# McPiFace-Pi4-Status-V3.net
KiCad netlist of a schematic drawn in EAGLE
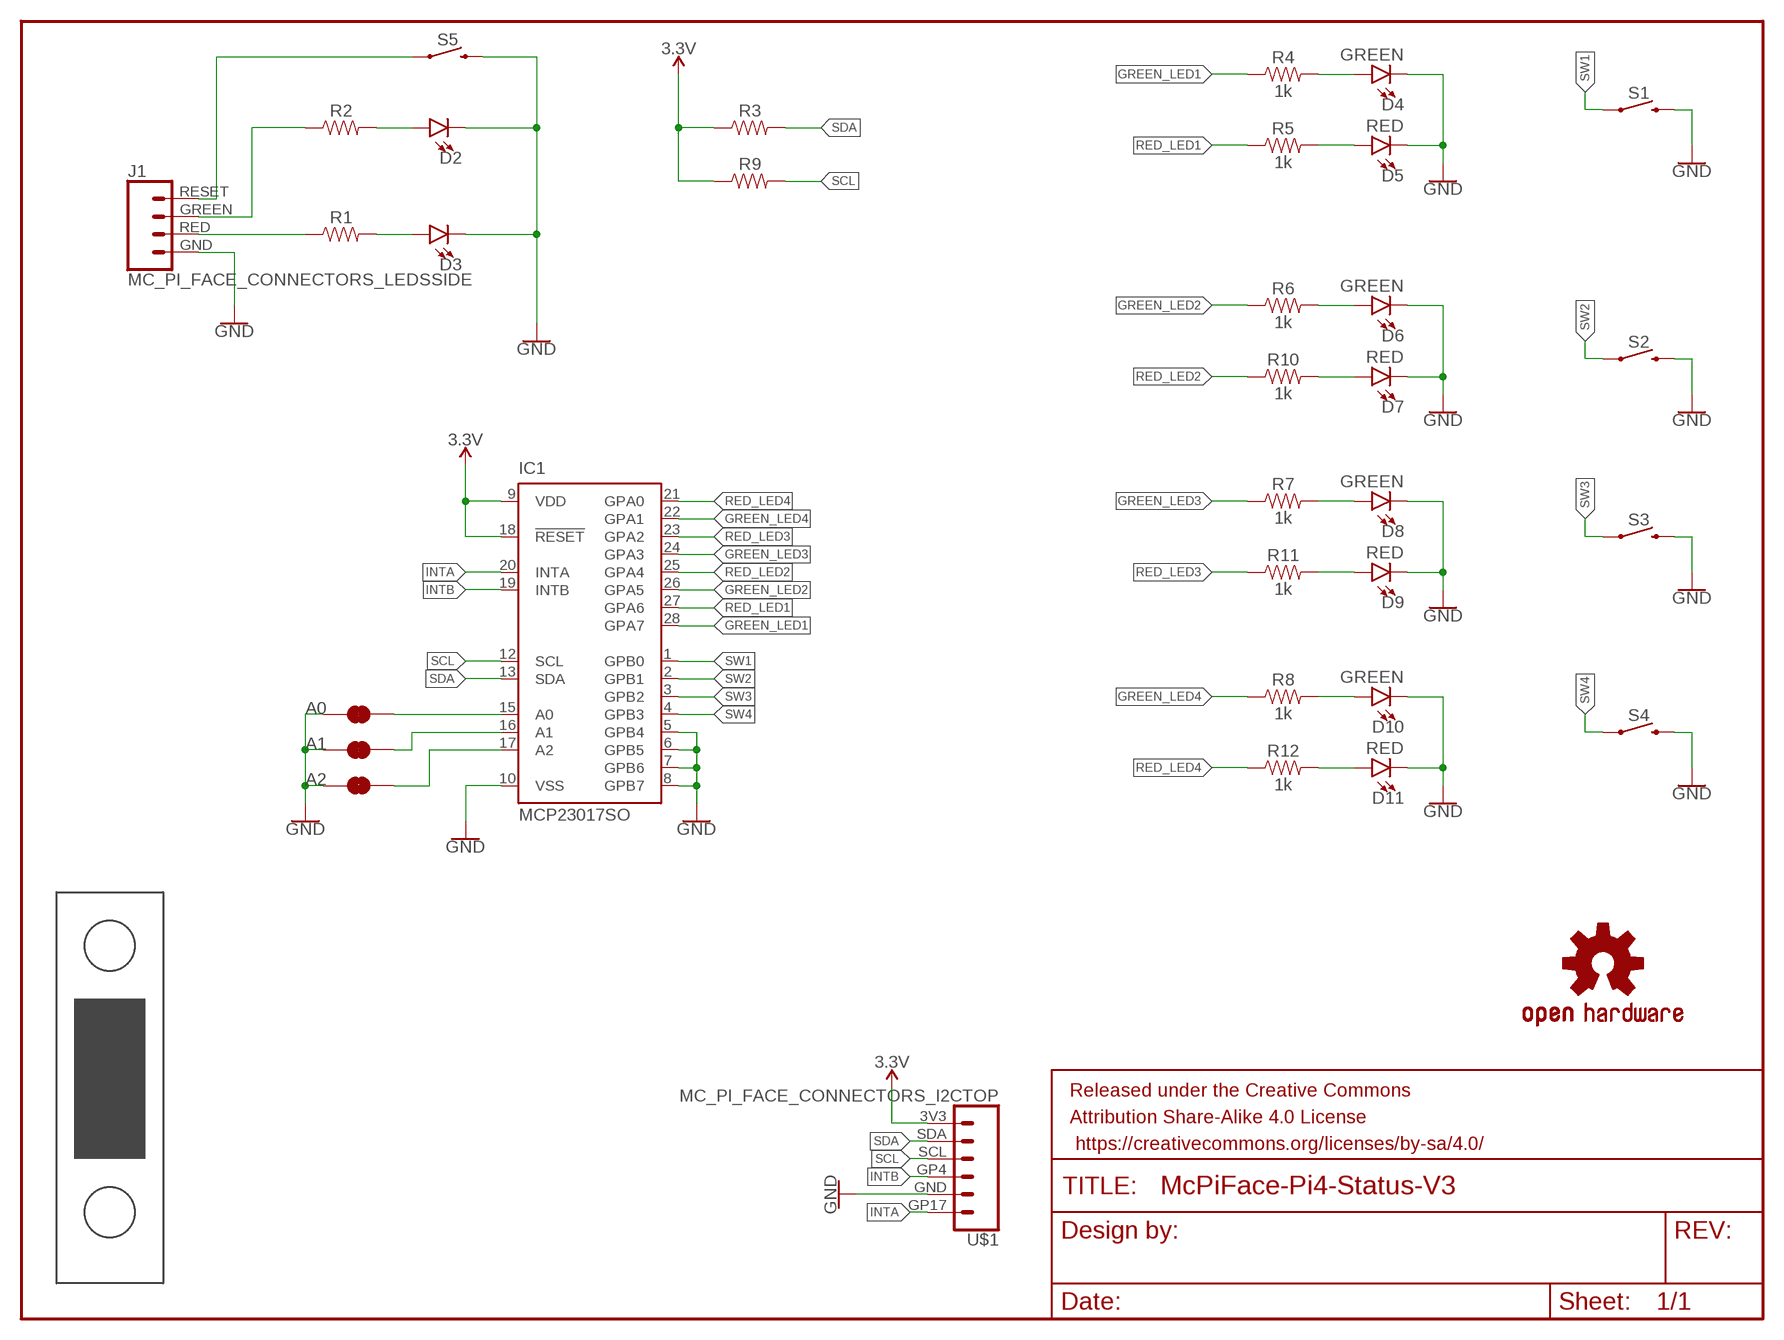
[diagram p0: schematic, sheet 1]

(export (version "E")
  (design (tool "Eeschema 10.0.6"))
  (components
    (comp (ref "A0")
      (value "JUMPER-SMT_2_NC_TRACE_SILK")
      (footprint "eagle-import:SMT-JUMPER_2_NC_TRACE_SILK")
      (libsource (lib "eagle-import") (part "JUMPER-SMT_2_NC_TRACE_SILK"))
    )
    (comp (ref "A1")
      (value "JUMPER-SMT_2_NC_TRACE_SILK")
      (footprint "eagle-import:SMT-JUMPER_2_NC_TRACE_SILK")
      (libsource (lib "eagle-import") (part "JUMPER-SMT_2_NC_TRACE_SILK"))
    )
    (comp (ref "A2")
      (value "JUMPER-SMT_2_NC_TRACE_SILK")
      (footprint "eagle-import:SMT-JUMPER_2_NC_TRACE_SILK")
      (libsource (lib "eagle-import") (part "JUMPER-SMT_2_NC_TRACE_SILK"))
    )
    (comp (ref "D2")
      (value "LEDLED-1206-BOTTOM-2.0MM-GREEN")
      (footprint "eagle-import:LED-1206-BOTTOM-2.0MM")
      (libsource (lib "eagle-import") (part "LEDLED-1206-BOTTOM-2.0MM-GREEN"))
    )
    (comp (ref "D3")
      (value "LEDLED-1206-BOTTOM-2.0MM-RED")
      (footprint "eagle-import:LED-1206-BOTTOM-2.0MM")
      (libsource (lib "eagle-import") (part "LEDLED-1206-BOTTOM-2.0MM-RED"))
    )
    (comp (ref "D4")
      (value "GREEN")
      (footprint "eagle-import:LED-1206-BOTTOM-2.0MM")
      (libsource (lib "eagle-import") (part "LEDLED-1206-BOTTOM-2.0MM-GREEN"))
    )
    (comp (ref "D5")
      (value "RED")
      (footprint "eagle-import:LED-1206-BOTTOM-2.0MM")
      (libsource (lib "eagle-import") (part "LEDLED-1206-BOTTOM-2.0MM-RED"))
    )
    (comp (ref "D6")
      (value "GREEN")
      (footprint "eagle-import:LED-1206-BOTTOM-2.0MM")
      (libsource (lib "eagle-import") (part "LEDLED-1206-BOTTOM-2.0MM-GREEN"))
    )
    (comp (ref "D7")
      (value "RED")
      (footprint "eagle-import:LED-1206-BOTTOM-2.0MM")
      (libsource (lib "eagle-import") (part "LEDLED-1206-BOTTOM-2.0MM-RED"))
    )
    (comp (ref "D8")
      (value "GREEN")
      (footprint "eagle-import:LED-1206-BOTTOM-2.0MM")
      (libsource (lib "eagle-import") (part "LEDLED-1206-BOTTOM-2.0MM-GREEN"))
    )
    (comp (ref "D9")
      (value "RED")
      (footprint "eagle-import:LED-1206-BOTTOM-2.0MM")
      (libsource (lib "eagle-import") (part "LEDLED-1206-BOTTOM-2.0MM-RED"))
    )
    (comp (ref "D10")
      (value "GREEN")
      (footprint "eagle-import:LED-1206-BOTTOM-2.0MM")
      (libsource (lib "eagle-import") (part "LEDLED-1206-BOTTOM-2.0MM-GREEN"))
    )
    (comp (ref "D11")
      (value "RED")
      (footprint "eagle-import:LED-1206-BOTTOM-2.0MM")
      (libsource (lib "eagle-import") (part "LEDLED-1206-BOTTOM-2.0MM-RED"))
    )
    (comp (ref "FP1")
      (value "MC_PI_4_FACE_PANELDOUBLE")
      (footprint "eagle-import:MC_PI_4-DOUBLE_FACE")
      (libsource (lib "eagle-import") (part "MC_PI_4_FACE_PANELDOUBLE"))
    )
    (comp (ref "FRAME1")
      (value "FRAME-LETTER")
      (footprint "eagle-import:CREATIVE_COMMONS")
      (libsource (lib "eagle-import") (part "FRAME-LETTER"))
    )
    (comp (ref "IC1")
      (value "MCP23017SO")
      (footprint "eagle-import:SO28W")
      (libsource (lib "eagle-import") (part "MCP23017SO"))
    )
    (comp (ref "J1")
      (value "MC_PI_FACE_CONNECTORS_LEDSSIDE")
      (footprint "eagle-import:JST-4-SH-1.0MM-SIDE")
      (fields (field (name "MFG") "SM04B-SRSS-TB(LF)(SN)"))
      (libsource (lib "eagle-import") (part "MC_PI_FACE_CONNECTORS_LEDSSIDE"))
    )
    (comp (ref "LOGO1")
      (value "OSHW-LOGOL")
      (footprint "eagle-import:OSHW-LOGO-L")
      (libsource (lib "eagle-import") (part "OSHW-LOGOL"))
    )
    (comp (ref "R1")
      (value "RESISTOR0805")
      (footprint "eagle-import:0805")
      (libsource (lib "eagle-import") (part "RESISTOR0805"))
    )
    (comp (ref "R2")
      (value "RESISTOR0805")
      (footprint "eagle-import:0805")
      (libsource (lib "eagle-import") (part "RESISTOR0805"))
    )
    (comp (ref "R3")
      (value "RESISTOR0805")
      (footprint "eagle-import:0805")
      (libsource (lib "eagle-import") (part "RESISTOR0805"))
    )
    (comp (ref "R4")
      (value "1k")
      (footprint "eagle-import:0805")
      (libsource (lib "eagle-import") (part "RESISTOR0805"))
    )
    (comp (ref "R5")
      (value "1k")
      (footprint "eagle-import:0805")
      (libsource (lib "eagle-import") (part "RESISTOR0805"))
    )
    (comp (ref "R6")
      (value "1k")
      (footprint "eagle-import:0805")
      (libsource (lib "eagle-import") (part "RESISTOR0805"))
    )
    (comp (ref "R7")
      (value "1k")
      (footprint "eagle-import:0805")
      (libsource (lib "eagle-import") (part "RESISTOR0805"))
    )
    (comp (ref "R8")
      (value "1k")
      (footprint "eagle-import:0805")
      (libsource (lib "eagle-import") (part "RESISTOR0805"))
    )
    (comp (ref "R9")
      (value "RESISTOR0805")
      (footprint "eagle-import:0805")
      (libsource (lib "eagle-import") (part "RESISTOR0805"))
    )
    (comp (ref "R10")
      (value "1k")
      (footprint "eagle-import:0805")
      (libsource (lib "eagle-import") (part "RESISTOR0805"))
    )
    (comp (ref "R11")
      (value "1k")
      (footprint "eagle-import:0805")
      (libsource (lib "eagle-import") (part "RESISTOR0805"))
    )
    (comp (ref "R12")
      (value "1k")
      (footprint "eagle-import:0805")
      (libsource (lib "eagle-import") (part "RESISTOR0805"))
    )
    (comp (ref "S1")
      (value "MOMENTARY-SWITCH-SPSTTACKTILE_SWITCH_PTH_6.0MM_NO_TOP_RESIST")
      (footprint "eagle-import:TACTILE_SWITCH_PTH_6.0MM_NO_TOP_RESIST")
      (libsource (lib "eagle-import") (part "MOMENTARY-SWITCH-SPSTTACKTILE_SWITCH_PTH_6.0MM_NO_TOP_RESIST"))
    )
    (comp (ref "S2")
      (value "MOMENTARY-SWITCH-SPSTTACKTILE_SWITCH_PTH_6.0MM_NO_TOP_RESIST")
      (footprint "eagle-import:TACTILE_SWITCH_PTH_6.0MM_NO_TOP_RESIST")
      (libsource (lib "eagle-import") (part "MOMENTARY-SWITCH-SPSTTACKTILE_SWITCH_PTH_6.0MM_NO_TOP_RESIST"))
    )
    (comp (ref "S3")
      (value "MOMENTARY-SWITCH-SPSTTACKTILE_SWITCH_PTH_6.0MM_NO_TOP_RESIST")
      (footprint "eagle-import:TACTILE_SWITCH_PTH_6.0MM_NO_TOP_RESIST")
      (libsource (lib "eagle-import") (part "MOMENTARY-SWITCH-SPSTTACKTILE_SWITCH_PTH_6.0MM_NO_TOP_RESIST"))
    )
    (comp (ref "S4")
      (value "MOMENTARY-SWITCH-SPSTTACKTILE_SWITCH_PTH_6.0MM_NO_TOP_RESIST")
      (footprint "eagle-import:TACTILE_SWITCH_PTH_6.0MM_NO_TOP_RESIST")
      (libsource (lib "eagle-import") (part "MOMENTARY-SWITCH-SPSTTACKTILE_SWITCH_PTH_6.0MM_NO_TOP_RESIST"))
    )
    (comp (ref "S5")
      (value "MOMENTARY-SWITCH-SPSTTACKTILE_SWITCH_PTH_6.0MM_NO_TOP_RESIST")
      (footprint "eagle-import:TACTILE_SWITCH_PTH_6.0MM_NO_TOP_RESIST")
      (libsource (lib "eagle-import") (part "MOMENTARY-SWITCH-SPSTTACKTILE_SWITCH_PTH_6.0MM_NO_TOP_RESIST"))
    )
    (comp (ref "U$1")
      (value "MC_PI_FACE_CONNECTORS_I2CTOP")
      (footprint "eagle-import:JST-6-SH-1.0MM-TOP")
      (libsource (lib "eagle-import") (part "MC_PI_FACE_CONNECTORS_I2CTOP"))
    )
  )
  (nets
    (net (code "1") (name "3.3V") (class "Default")
      (node (ref "IC1") (pin "18") (pinfunction "~{RESET}_18") (pintype "input"))
      (node (ref "IC1") (pin "9") (pinfunction "VDD_9") (pintype "power_in"))
      (node (ref "R3") (pin "1") (pinfunction "1_1") (pintype "passive"))
      (node (ref "R9") (pin "1") (pinfunction "1_1") (pintype "passive"))
      (node (ref "U$1") (pin "3V3") (pinfunction "3V3_3V3") (pintype "power_in"))
    )
    (net (code "2") (name "GND") (class "Default")
      (node (ref "A0") (pin "1") (pinfunction "1_1") (pintype "passive"))
      (node (ref "A1") (pin "1") (pinfunction "1_1") (pintype "passive"))
      (node (ref "A2") (pin "1") (pinfunction "1_1") (pintype "passive"))
      (node (ref "D10") (pin "C") (pinfunction "C_C") (pintype "passive"))
      (node (ref "D11") (pin "C") (pinfunction "C_C") (pintype "passive"))
      (node (ref "D2") (pin "C") (pinfunction "C_C") (pintype "passive"))
      (node (ref "D3") (pin "C") (pinfunction "C_C") (pintype "passive"))
      (node (ref "D4") (pin "C") (pinfunction "C_C") (pintype "passive"))
      (node (ref "D5") (pin "C") (pinfunction "C_C") (pintype "passive"))
      (node (ref "D6") (pin "C") (pinfunction "C_C") (pintype "passive"))
      (node (ref "D7") (pin "C") (pinfunction "C_C") (pintype "passive"))
      (node (ref "D8") (pin "C") (pinfunction "C_C") (pintype "passive"))
      (node (ref "D9") (pin "C") (pinfunction "C_C") (pintype "passive"))
      (node (ref "IC1") (pin "10") (pinfunction "VSS_10") (pintype "power_in"))
      (node (ref "IC1") (pin "5") (pinfunction "GPB4_5") (pintype "bidirectional"))
      (node (ref "IC1") (pin "6") (pinfunction "GPB5_6") (pintype "bidirectional"))
      (node (ref "IC1") (pin "7") (pinfunction "GPB6_7") (pintype "bidirectional"))
      (node (ref "IC1") (pin "8") (pinfunction "GPB7_8") (pintype "bidirectional"))
      (node (ref "J1") (pin "GND") (pinfunction "GND_GND") (pintype "power_in"))
      (node (ref "S1") (pin "3") (pinfunction "2_3") (pintype "passive"))
      (node (ref "S2") (pin "3") (pinfunction "2_3") (pintype "passive"))
      (node (ref "S3") (pin "3") (pinfunction "2_3") (pintype "passive"))
      (node (ref "S4") (pin "3") (pinfunction "2_3") (pintype "passive"))
      (node (ref "S5") (pin "3") (pinfunction "2_3") (pintype "passive"))
      (node (ref "U$1") (pin "GND") (pinfunction "GND_GND") (pintype "power_in"))
    )
    (net (code "3") (name "GREEN_LED1") (class "Default")
      (node (ref "IC1") (pin "28") (pinfunction "GPA7_28") (pintype "bidirectional"))
      (node (ref "R4") (pin "1") (pinfunction "1_1") (pintype "passive"))
    )
    (net (code "4") (name "GREEN_LED2") (class "Default")
      (node (ref "IC1") (pin "26") (pinfunction "GPA5_26") (pintype "bidirectional"))
      (node (ref "R6") (pin "1") (pinfunction "1_1") (pintype "passive"))
    )
    (net (code "5") (name "GREEN_LED3") (class "Default")
      (node (ref "IC1") (pin "24") (pinfunction "GPA3_24") (pintype "bidirectional"))
      (node (ref "R7") (pin "1") (pinfunction "1_1") (pintype "passive"))
    )
    (net (code "6") (name "GREEN_LED4") (class "Default")
      (node (ref "IC1") (pin "22") (pinfunction "GPA1_22") (pintype "bidirectional"))
      (node (ref "R8") (pin "1") (pinfunction "1_1") (pintype "passive"))
    )
    (net (code "7") (name "INTA") (class "Default")
      (node (ref "IC1") (pin "20") (pinfunction "INTA_20") (pintype "output"))
      (node (ref "U$1") (pin "GP17") (pinfunction "GP17_GP17") (pintype "bidirectional"))
    )
    (net (code "8") (name "INTB") (class "Default")
      (node (ref "IC1") (pin "19") (pinfunction "INTB_19") (pintype "output"))
      (node (ref "U$1") (pin "GP4") (pinfunction "GP4_GP4") (pintype "bidirectional"))
    )
    (net (code "9") (name "Net-(D2-PadA)") (class "Default")
      (node (ref "D2") (pin "A") (pinfunction "A_A") (pintype "passive"))
      (node (ref "R2") (pin "2") (pinfunction "2_2") (pintype "passive"))
    )
    (net (code "10") (name "Net-(D3-PadA)") (class "Default")
      (node (ref "D3") (pin "A") (pinfunction "A_A") (pintype "passive"))
      (node (ref "R1") (pin "2") (pinfunction "2_2") (pintype "passive"))
    )
    (net (code "11") (name "Net-(D4-PadA)") (class "Default")
      (node (ref "D4") (pin "A") (pinfunction "A_A") (pintype "passive"))
      (node (ref "R4") (pin "2") (pinfunction "2_2") (pintype "passive"))
    )
    (net (code "12") (name "Net-(D5-PadA)") (class "Default")
      (node (ref "D5") (pin "A") (pinfunction "A_A") (pintype "passive"))
      (node (ref "R5") (pin "2") (pinfunction "2_2") (pintype "passive"))
    )
    (net (code "13") (name "Net-(D6-PadA)") (class "Default")
      (node (ref "D6") (pin "A") (pinfunction "A_A") (pintype "passive"))
      (node (ref "R6") (pin "2") (pinfunction "2_2") (pintype "passive"))
    )
    (net (code "14") (name "Net-(D7-PadA)") (class "Default")
      (node (ref "D7") (pin "A") (pinfunction "A_A") (pintype "passive"))
      (node (ref "R10") (pin "2") (pinfunction "2_2") (pintype "passive"))
    )
    (net (code "15") (name "Net-(D8-PadA)") (class "Default")
      (node (ref "D8") (pin "A") (pinfunction "A_A") (pintype "passive"))
      (node (ref "R7") (pin "2") (pinfunction "2_2") (pintype "passive"))
    )
    (net (code "16") (name "Net-(D9-PadA)") (class "Default")
      (node (ref "D9") (pin "A") (pinfunction "A_A") (pintype "passive"))
      (node (ref "R11") (pin "2") (pinfunction "2_2") (pintype "passive"))
    )
    (net (code "17") (name "Net-(D10-PadA)") (class "Default")
      (node (ref "D10") (pin "A") (pinfunction "A_A") (pintype "passive"))
      (node (ref "R8") (pin "2") (pinfunction "2_2") (pintype "passive"))
    )
    (net (code "18") (name "Net-(D11-PadA)") (class "Default")
      (node (ref "D11") (pin "A") (pinfunction "A_A") (pintype "passive"))
      (node (ref "R12") (pin "2") (pinfunction "2_2") (pintype "passive"))
    )
    (net (code "19") (name "Net-(IC1-A0)") (class "Default")
      (node (ref "A0") (pin "2") (pinfunction "2_2") (pintype "passive"))
      (node (ref "IC1") (pin "15") (pinfunction "A0_15") (pintype "input"))
    )
    (net (code "20") (name "Net-(IC1-A1)") (class "Default")
      (node (ref "A1") (pin "2") (pinfunction "2_2") (pintype "passive"))
      (node (ref "IC1") (pin "16") (pinfunction "A1_16") (pintype "input"))
    )
    (net (code "21") (name "Net-(IC1-A2)") (class "Default")
      (node (ref "A2") (pin "2") (pinfunction "2_2") (pintype "passive"))
      (node (ref "IC1") (pin "17") (pinfunction "A2_17") (pintype "input"))
    )
    (net (code "22") (name "Net-(J1-PadGREEN)") (class "Default")
      (node (ref "J1") (pin "GREEN") (pinfunction "GREEN_GREEN") (pintype "passive"))
      (node (ref "R2") (pin "1") (pinfunction "1_1") (pintype "passive"))
    )
    (net (code "23") (name "Net-(J1-PadRED)") (class "Default")
      (node (ref "J1") (pin "RED") (pinfunction "RED_RED") (pintype "passive"))
      (node (ref "R1") (pin "1") (pinfunction "1_1") (pintype "passive"))
    )
    (net (code "24") (name "Net-(J1-PadRESET)") (class "Default")
      (node (ref "J1") (pin "RESET") (pinfunction "RESET_RESET") (pintype "passive"))
      (node (ref "S5") (pin "1") (pinfunction "1_1") (pintype "passive"))
    )
    (net (code "25") (name "RED_LED1") (class "Default")
      (node (ref "IC1") (pin "27") (pinfunction "GPA6_27") (pintype "bidirectional"))
      (node (ref "R5") (pin "1") (pinfunction "1_1") (pintype "passive"))
    )
    (net (code "26") (name "RED_LED2") (class "Default")
      (node (ref "IC1") (pin "25") (pinfunction "GPA4_25") (pintype "bidirectional"))
      (node (ref "R10") (pin "1") (pinfunction "1_1") (pintype "passive"))
    )
    (net (code "27") (name "RED_LED3") (class "Default")
      (node (ref "IC1") (pin "23") (pinfunction "GPA2_23") (pintype "bidirectional"))
      (node (ref "R11") (pin "1") (pinfunction "1_1") (pintype "passive"))
    )
    (net (code "28") (name "RED_LED4") (class "Default")
      (node (ref "IC1") (pin "21") (pinfunction "GPA0_21") (pintype "bidirectional"))
      (node (ref "R12") (pin "1") (pinfunction "1_1") (pintype "passive"))
    )
    (net (code "29") (name "SCL") (class "Default")
      (node (ref "IC1") (pin "12") (pinfunction "SCL_12") (pintype "input"))
      (node (ref "R9") (pin "2") (pinfunction "2_2") (pintype "passive"))
      (node (ref "U$1") (pin "SCL") (pinfunction "SCL_SCL") (pintype "bidirectional"))
    )
    (net (code "30") (name "SDA") (class "Default")
      (node (ref "IC1") (pin "13") (pinfunction "SDA_13") (pintype "bidirectional"))
      (node (ref "R3") (pin "2") (pinfunction "2_2") (pintype "passive"))
      (node (ref "U$1") (pin "SDA") (pinfunction "SDA_SDA") (pintype "bidirectional"))
    )
    (net (code "31") (name "SW1") (class "Default")
      (node (ref "IC1") (pin "1") (pinfunction "GPB0_1") (pintype "bidirectional"))
      (node (ref "S1") (pin "1") (pinfunction "1_1") (pintype "passive"))
    )
    (net (code "32") (name "SW2") (class "Default")
      (node (ref "IC1") (pin "2") (pinfunction "GPB1_2") (pintype "bidirectional"))
      (node (ref "S2") (pin "1") (pinfunction "1_1") (pintype "passive"))
    )
    (net (code "33") (name "SW3") (class "Default")
      (node (ref "IC1") (pin "3") (pinfunction "GPB2_3") (pintype "bidirectional"))
      (node (ref "S3") (pin "1") (pinfunction "1_1") (pintype "passive"))
    )
    (net (code "34") (name "SW4") (class "Default")
      (node (ref "IC1") (pin "4") (pinfunction "GPB3_4") (pintype "bidirectional"))
      (node (ref "S4") (pin "1") (pinfunction "1_1") (pintype "passive"))
    )
  )
)
